# Power.net
KiCad netlist of a schematic drawn in Altium Designer
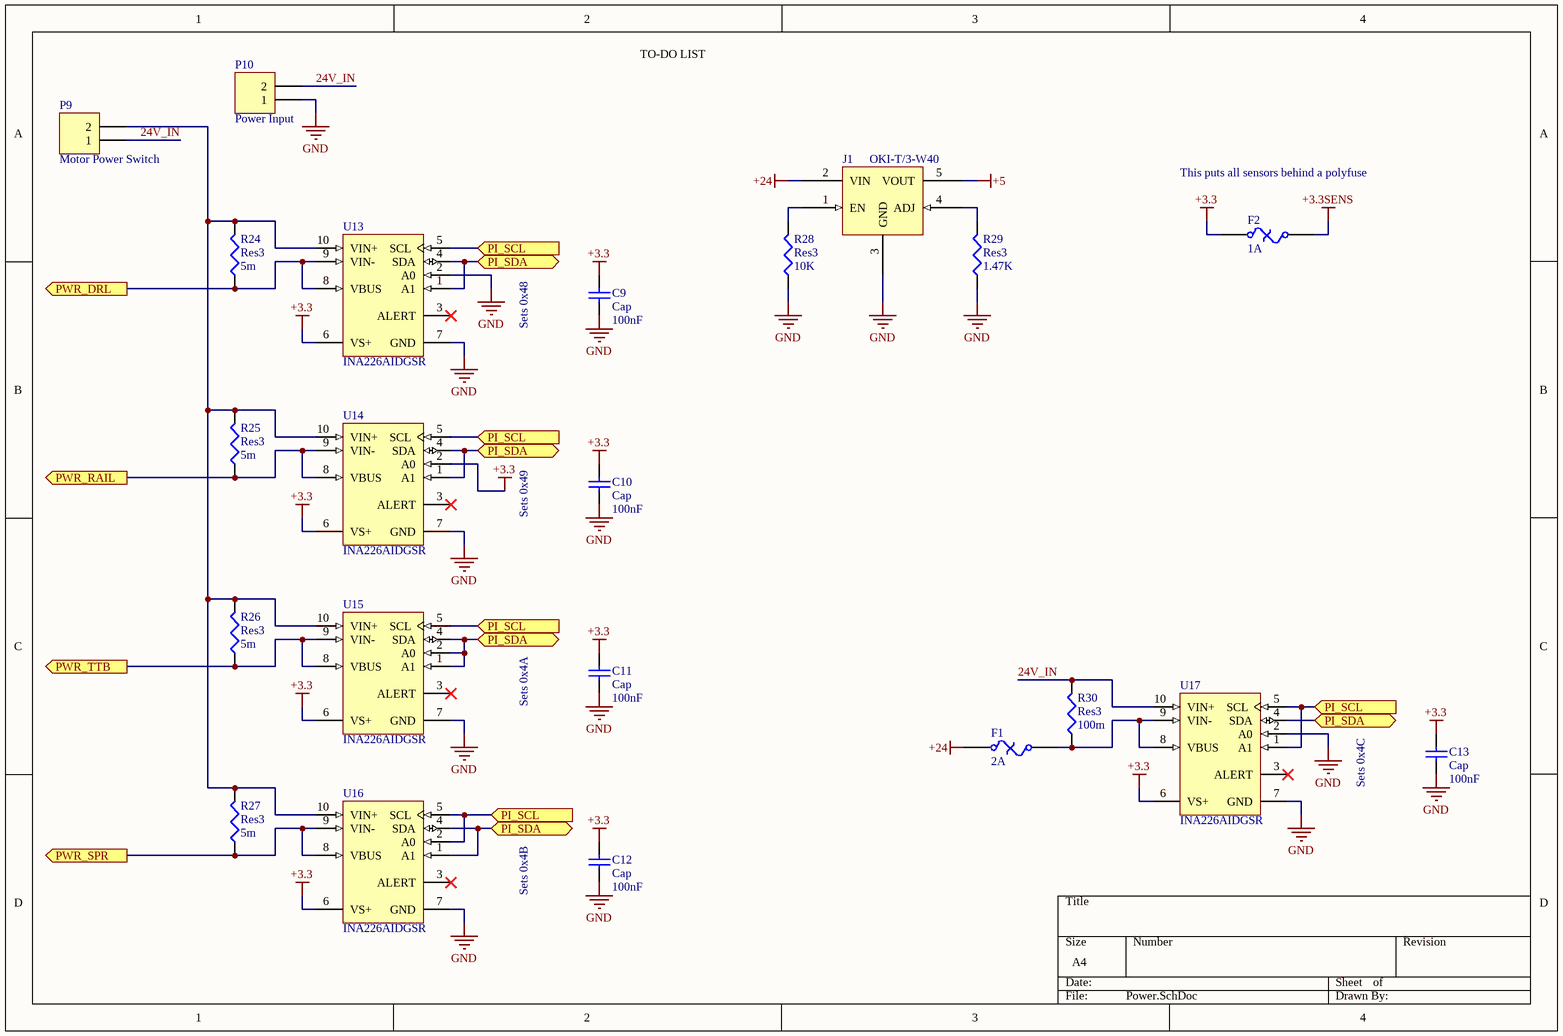
[diagram p0: Power.SchDoc]

(export (version "E")
  (design (tool "Eeschema 10.0.6"))
  (components
    (comp (ref "C9")
      (value "Cap")
      (footprint "C0805")
      (description "Capacitor")
      (fields (field (name "ALTIUM_VALUE") "100nF") (field (name "PUBLISHER") "Altium Limited"))
      (libsource (lib "Miscellaneous Devices") (part "Cap"))
    )
    (comp (ref "C10")
      (value "Cap")
      (footprint "C0805")
      (description "Capacitor")
      (fields (field (name "ALTIUM_VALUE") "100nF") (field (name "PUBLISHER") "Altium Limited"))
      (libsource (lib "Miscellaneous Devices") (part "Cap"))
    )
    (comp (ref "C11")
      (value "Cap")
      (footprint "C0805")
      (description "Capacitor")
      (fields (field (name "ALTIUM_VALUE") "100nF") (field (name "PUBLISHER") "Altium Limited"))
      (libsource (lib "Miscellaneous Devices") (part "Cap"))
    )
    (comp (ref "C12")
      (value "Cap")
      (footprint "C0805")
      (description "Capacitor")
      (fields (field (name "ALTIUM_VALUE") "100nF") (field (name "PUBLISHER") "Altium Limited"))
      (libsource (lib "Miscellaneous Devices") (part "Cap"))
    )
    (comp (ref "C13")
      (value "Cap")
      (footprint "C0805")
      (description "Capacitor")
      (fields (field (name "ALTIUM_VALUE") "100nF") (field (name "PUBLISHER") "Altium Limited"))
      (libsource (lib "Miscellaneous Devices") (part "Cap"))
    )
    (comp (ref "F1")
      (value "2A")
      (footprint "2920")
      (description "Thermal Fuse")
      (fields (field (name "PUBLISHER") "Altium Limited"))
      (libsource (lib "Miscellaneous Devices") (part "Fuse Thermal"))
    )
    (comp (ref "F2")
      (value "1A")
      (footprint "2920")
      (description "Thermal Fuse")
      (fields (field (name "PUBLISHER") "Altium Limited"))
      (libsource (lib "Miscellaneous Devices") (part "Fuse Thermal"))
    )
    (comp (ref "J1")
      (value "OKI-T/3-W40")
      (footprint "OKI-T/3-W40")
      (description "Adjustable Output 3-Amp DOSA-SMT DC/DC Converters")
      (libsource (lib "ScienceSymbols") (part "OKI-T/3-W40"))
    )
    (comp (ref "P9")
      (value "Motor Power Switch")
      (footprint "SuperSabre-2pos")
      (description "Header, 2-Pin")
      (fields (field (name "PUBLISHER") "Altium Limited"))
      (libsource (lib "Miscellaneous Connectors") (part "Header 2"))
    )
    (comp (ref "P10")
      (value "Power Input")
      (footprint "SuperSabre-2pos")
      (description "Header, 2-Pin")
      (fields (field (name "PUBLISHER") "Altium Limited"))
      (libsource (lib "Miscellaneous Connectors") (part "Header 2"))
    )
    (comp (ref "R24")
      (value "Res3")
      (footprint "FCSL110")
      (description "Resistor")
      (fields (field (name "ALTIUM_VALUE") "5m") (field (name "PUBLISHER") "Altium Limited"))
      (libsource (lib "Miscellaneous Devices") (part "Res3"))
    )
    (comp (ref "R25")
      (value "Res3")
      (footprint "FCSL110")
      (description "Resistor")
      (fields (field (name "ALTIUM_VALUE") "5m") (field (name "PUBLISHER") "Altium Limited"))
      (libsource (lib "Miscellaneous Devices") (part "Res3"))
    )
    (comp (ref "R26")
      (value "Res3")
      (footprint "FCSL110")
      (description "Resistor")
      (fields (field (name "ALTIUM_VALUE") "5m") (field (name "PUBLISHER") "Altium Limited"))
      (libsource (lib "Miscellaneous Devices") (part "Res3"))
    )
    (comp (ref "R27")
      (value "Res3")
      (footprint "FCSL110")
      (description "Resistor")
      (fields (field (name "ALTIUM_VALUE") "5m") (field (name "PUBLISHER") "Altium Limited"))
      (libsource (lib "Miscellaneous Devices") (part "Res3"))
    )
    (comp (ref "R28")
      (value "Res3")
      (footprint "C0805")
      (description "Resistor")
      (fields (field (name "ALTIUM_VALUE") "10K") (field (name "PUBLISHER") "Altium Limited"))
      (libsource (lib "Miscellaneous Devices") (part "Res3"))
    )
    (comp (ref "R29")
      (value "Res3")
      (footprint "C0805")
      (description "Resistor")
      (fields (field (name "ALTIUM_VALUE") "1.47K") (field (name "PUBLISHER") "Altium Limited"))
      (libsource (lib "Miscellaneous Devices") (part "Res3"))
    )
    (comp (ref "R30")
      (value "Res3")
      (footprint "RW5S0")
      (description "Resistor")
      (fields (field (name "ALTIUM_VALUE") "100m") (field (name "PUBLISHER") "Altium Limited"))
      (libsource (lib "Miscellaneous Devices") (part "Res3"))
    )
    (comp (ref "U13")
      (value "INA226AIDGSR")
      (footprint "DGS0010A_L")
      (libsource (lib "Altium Content Vault") (part "TI-INA226DGS10"))
    )
    (comp (ref "U14")
      (value "INA226AIDGSR")
      (footprint "DGS0010A_L")
      (libsource (lib "Altium Content Vault") (part "TI-INA226DGS10"))
    )
    (comp (ref "U15")
      (value "INA226AIDGSR")
      (footprint "DGS0010A_L")
      (libsource (lib "Altium Content Vault") (part "TI-INA226DGS10"))
    )
    (comp (ref "U16")
      (value "INA226AIDGSR")
      (footprint "DGS0010A_L")
      (libsource (lib "Altium Content Vault") (part "TI-INA226DGS10"))
    )
    (comp (ref "U17")
      (value "INA226AIDGSR")
      (footprint "DGS0010A_L")
      (libsource (lib "Altium Content Vault") (part "TI-INA226DGS10"))
    )
  )
  (nets
    (net (code "1") (name "+3.3") (class "Default")
      (node (ref "C10") (pin "2") (pinfunction "2_2") (pintype "passive"))
      (node (ref "C11") (pin "2") (pinfunction "2_2") (pintype "passive"))
      (node (ref "C12") (pin "2") (pinfunction "2_2") (pintype "passive"))
      (node (ref "C13") (pin "2") (pinfunction "2_2") (pintype "passive"))
      (node (ref "C9") (pin "2") (pinfunction "2_2") (pintype "passive"))
      (node (ref "F2") (pin "1") (pinfunction "1_1") (pintype "passive"))
      (node (ref "U13") (pin "6") (pinfunction "VS+_6") (pintype "power_in"))
      (node (ref "U14") (pin "2") (pinfunction "A0_2") (pintype "input"))
      (node (ref "U14") (pin "6") (pinfunction "VS+_6") (pintype "power_in"))
      (node (ref "U15") (pin "6") (pinfunction "VS+_6") (pintype "power_in"))
      (node (ref "U16") (pin "6") (pinfunction "VS+_6") (pintype "power_in"))
      (node (ref "U17") (pin "6") (pinfunction "VS+_6") (pintype "power_in"))
    )
    (net (code "2") (name "+3.3SENS") (class "Default")
      (node (ref "F2") (pin "2") (pinfunction "2_2") (pintype "passive"))
    )
    (net (code "3") (name "+5") (class "Default")
      (node (ref "J1") (pin "5") (pinfunction "VOUT_5") (pintype "power_in"))
    )
    (net (code "4") (name "+24") (class "Default")
      (node (ref "F1") (pin "1") (pinfunction "1_1") (pintype "passive"))
      (node (ref "J1") (pin "2") (pinfunction "VIN_2") (pintype "power_in"))
    )
    (net (code "5") (name "/24V_IN") (class "Default")
      (node (ref "P10") (pin "2") (pinfunction "2_2") (pintype "passive"))
      (node (ref "P9") (pin "1") (pinfunction "1_1") (pintype "passive"))
      (node (ref "R30") (pin "2") (pinfunction "2_2") (pintype "passive"))
      (node (ref "U17") (pin "10") (pinfunction "VIN+_10") (pintype "input"))
    )
    (net (code "6") (name "/PI_SCL") (class "Default")
      (node (ref "U13") (pin "5") (pinfunction "SCL_5") (pintype "input"))
      (node (ref "U14") (pin "5") (pinfunction "SCL_5") (pintype "input"))
      (node (ref "U15") (pin "5") (pinfunction "SCL_5") (pintype "input"))
      (node (ref "U16") (pin "2") (pinfunction "A0_2") (pintype "input"))
      (node (ref "U16") (pin "5") (pinfunction "SCL_5") (pintype "input"))
      (node (ref "U17") (pin "1") (pinfunction "A1_1") (pintype "input"))
      (node (ref "U17") (pin "5") (pinfunction "SCL_5") (pintype "input"))
    )
    (net (code "7") (name "/PI_SDA") (class "Default")
      (node (ref "U13") (pin "1") (pinfunction "A1_1") (pintype "input"))
      (node (ref "U13") (pin "4") (pinfunction "SDA_4") (pintype "bidirectional"))
      (node (ref "U14") (pin "1") (pinfunction "A1_1") (pintype "input"))
      (node (ref "U14") (pin "4") (pinfunction "SDA_4") (pintype "bidirectional"))
      (node (ref "U15") (pin "1") (pinfunction "A1_1") (pintype "input"))
      (node (ref "U15") (pin "2") (pinfunction "A0_2") (pintype "input"))
      (node (ref "U15") (pin "4") (pinfunction "SDA_4") (pintype "bidirectional"))
      (node (ref "U16") (pin "1") (pinfunction "A1_1") (pintype "input"))
      (node (ref "U16") (pin "4") (pinfunction "SDA_4") (pintype "bidirectional"))
      (node (ref "U17") (pin "4") (pinfunction "SDA_4") (pintype "bidirectional"))
    )
    (net (code "8") (name "/PWR_DRL") (class "Default")
      (node (ref "R24") (pin "1") (pinfunction "1_1") (pintype "passive"))
      (node (ref "U13") (pin "8") (pinfunction "VBUS_8") (pintype "input"))
      (node (ref "U13") (pin "9") (pinfunction "VIN-_9") (pintype "input"))
    )
    (net (code "9") (name "/PWR_RAIL") (class "Default")
      (node (ref "R25") (pin "1") (pinfunction "1_1") (pintype "passive"))
      (node (ref "U14") (pin "8") (pinfunction "VBUS_8") (pintype "input"))
      (node (ref "U14") (pin "9") (pinfunction "VIN-_9") (pintype "input"))
    )
    (net (code "10") (name "/PWR_SPR") (class "Default")
      (node (ref "R27") (pin "1") (pinfunction "1_1") (pintype "passive"))
      (node (ref "U16") (pin "8") (pinfunction "VBUS_8") (pintype "input"))
      (node (ref "U16") (pin "9") (pinfunction "VIN-_9") (pintype "input"))
    )
    (net (code "11") (name "/PWR_TTB") (class "Default")
      (node (ref "R26") (pin "1") (pinfunction "1_1") (pintype "passive"))
      (node (ref "U15") (pin "8") (pinfunction "VBUS_8") (pintype "input"))
      (node (ref "U15") (pin "9") (pinfunction "VIN-_9") (pintype "input"))
    )
    (net (code "12") (name "GND") (class "Default")
      (node (ref "C10") (pin "1") (pinfunction "1_1") (pintype "passive"))
      (node (ref "C11") (pin "1") (pinfunction "1_1") (pintype "passive"))
      (node (ref "C12") (pin "1") (pinfunction "1_1") (pintype "passive"))
      (node (ref "C13") (pin "1") (pinfunction "1_1") (pintype "passive"))
      (node (ref "C9") (pin "1") (pinfunction "1_1") (pintype "passive"))
      (node (ref "J1") (pin "3") (pinfunction "GND_3") (pintype "power_in"))
      (node (ref "P10") (pin "1") (pinfunction "1_1") (pintype "passive"))
      (node (ref "R28") (pin "1") (pinfunction "1_1") (pintype "passive"))
      (node (ref "R29") (pin "1") (pinfunction "1_1") (pintype "passive"))
      (node (ref "U13") (pin "2") (pinfunction "A0_2") (pintype "input"))
      (node (ref "U13") (pin "7") (pinfunction "GND_7") (pintype "power_in"))
      (node (ref "U14") (pin "7") (pinfunction "GND_7") (pintype "power_in"))
      (node (ref "U15") (pin "7") (pinfunction "GND_7") (pintype "power_in"))
      (node (ref "U16") (pin "7") (pinfunction "GND_7") (pintype "power_in"))
      (node (ref "U17") (pin "2") (pinfunction "A0_2") (pintype "input"))
      (node (ref "U17") (pin "7") (pinfunction "GND_7") (pintype "power_in"))
    )
    (net (code "13") (name "Net-(J1-ADJ)") (class "Default")
      (node (ref "J1") (pin "4") (pinfunction "ADJ_4") (pintype "input"))
      (node (ref "R29") (pin "2") (pinfunction "2_2") (pintype "passive"))
    )
    (net (code "14") (name "Net-(J1-EN)") (class "Default")
      (node (ref "J1") (pin "1") (pinfunction "EN_1") (pintype "input"))
      (node (ref "R28") (pin "2") (pinfunction "2_2") (pintype "passive"))
    )
    (net (code "15") (name "Net-(U13-VIN+)") (class "Default")
      (node (ref "P9") (pin "2") (pinfunction "2_2") (pintype "passive"))
      (node (ref "R24") (pin "2") (pinfunction "2_2") (pintype "passive"))
      (node (ref "R25") (pin "2") (pinfunction "2_2") (pintype "passive"))
      (node (ref "R26") (pin "2") (pinfunction "2_2") (pintype "passive"))
      (node (ref "R27") (pin "2") (pinfunction "2_2") (pintype "passive"))
      (node (ref "U13") (pin "10") (pinfunction "VIN+_10") (pintype "input"))
      (node (ref "U14") (pin "10") (pinfunction "VIN+_10") (pintype "input"))
      (node (ref "U15") (pin "10") (pinfunction "VIN+_10") (pintype "input"))
      (node (ref "U16") (pin "10") (pinfunction "VIN+_10") (pintype "input"))
    )
    (net (code "16") (name "Net-(U17-VBUS)") (class "Default")
      (node (ref "F1") (pin "2") (pinfunction "2_2") (pintype "passive"))
      (node (ref "R30") (pin "1") (pinfunction "1_1") (pintype "passive"))
      (node (ref "U17") (pin "8") (pinfunction "VBUS_8") (pintype "input"))
      (node (ref "U17") (pin "9") (pinfunction "VIN-_9") (pintype "input"))
    )
    (net (code "17") (name "unconnected-(U13-ALERT-Pad3)") (class "Default")
      (node (ref "U13") (pin "3") (pinfunction "ALERT_3") (pintype "open_collector+no_connect"))
    )
    (net (code "18") (name "unconnected-(U14-ALERT-Pad3)") (class "Default")
      (node (ref "U14") (pin "3") (pinfunction "ALERT_3") (pintype "open_collector+no_connect"))
    )
    (net (code "19") (name "unconnected-(U15-ALERT-Pad3)") (class "Default")
      (node (ref "U15") (pin "3") (pinfunction "ALERT_3") (pintype "open_collector+no_connect"))
    )
    (net (code "20") (name "unconnected-(U16-ALERT-Pad3)") (class "Default")
      (node (ref "U16") (pin "3") (pinfunction "ALERT_3") (pintype "open_collector+no_connect"))
    )
    (net (code "21") (name "unconnected-(U17-ALERT-Pad3)") (class "Default")
      (node (ref "U17") (pin "3") (pinfunction "ALERT_3") (pintype "open_collector+no_connect"))
    )
  )
)
